# ADC-Front.net
KiCad netlist of a schematic drawn in Altium Designer
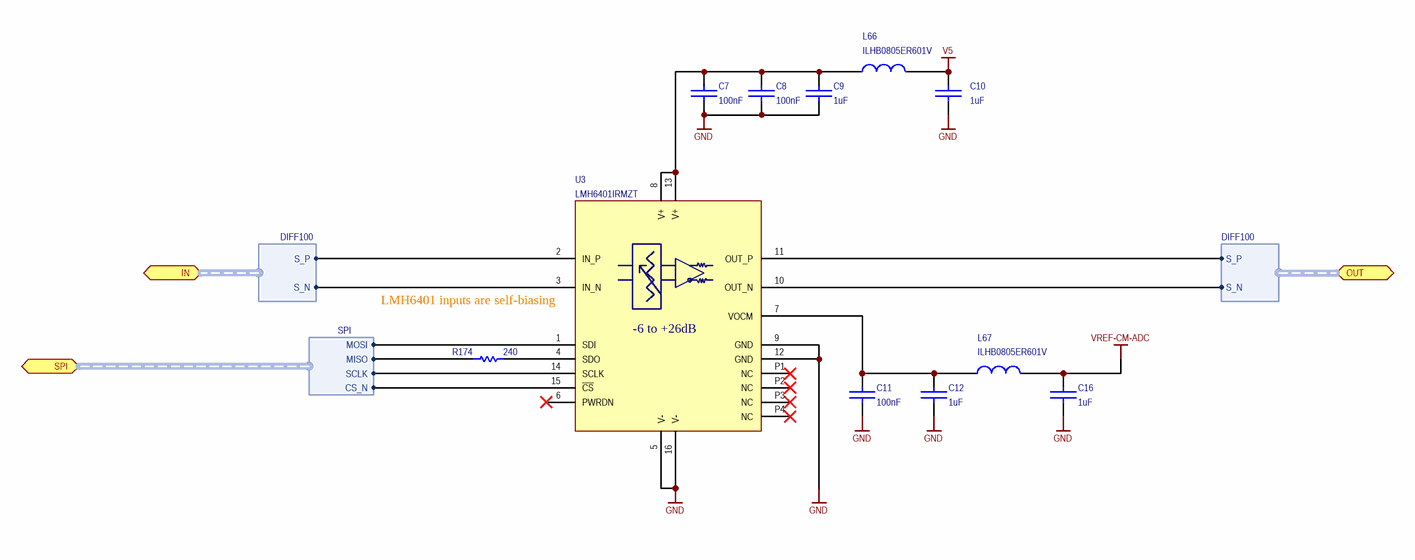
[diagram p0: ADC-Front.SchDoc]

(export (version "E")
  (design (tool "Eeschema 10.0.6"))
  (components
    (comp (ref "C7")
      (value "100nF")
      (footprint "generic:0402")
      (description "Ceramic Capacitor 100nF ±10% 16V X7R 0402")
      (fields (field (name "MANUFACTURER") "Murata") (field (name "VOLTAGE") "16V"))
      (libsource (lib "*") (part "CAP"))
    )
    (comp (ref "C8")
      (value "100nF")
      (footprint "generic:0402")
      (description "Ceramic Capacitor 100nF ±10% 16V X7R 0402")
      (fields (field (name "MANUFACTURER") "Murata") (field (name "VOLTAGE") "16V"))
      (libsource (lib "*") (part "CAP"))
    )
    (comp (ref "C9")
      (value "1uF")
      (footprint "generic:0402")
      (description "Ceramic Capacitor 1uF ±10% 10V X5R 0402")
      (fields (field (name "MANUFACTURER") "Murata") (field (name "TOLERANCE") "±10%"))
      (libsource (lib "*") (part "CAP"))
    )
    (comp (ref "C10")
      (value "1uF")
      (footprint "generic:0402")
      (description "Ceramic Capacitor 1uF ±10% 10V X5R 0402")
      (fields (field (name "MANUFACTURER") "Murata") (field (name "TOLERANCE") "±10%"))
      (libsource (lib "*") (part "CAP"))
    )
    (comp (ref "C11")
      (value "100nF")
      (footprint "generic:0402")
      (description "Ceramic Capacitor 100nF ±10% 16V X7R 0402")
      (fields (field (name "MANUFACTURER") "Murata") (field (name "VOLTAGE") "16V"))
      (libsource (lib "*") (part "CAP"))
    )
    (comp (ref "C12")
      (value "1uF")
      (footprint "generic:0402")
      (description "Ceramic Capacitor 1uF ±10% 10V X5R 0402")
      (fields (field (name "MANUFACTURER") "Murata") (field (name "TOLERANCE") "±10%"))
      (libsource (lib "*") (part "CAP"))
    )
    (comp (ref "C16")
      (value "1uF")
      (footprint "generic:0402")
      (description "Ceramic Capacitor 1uF ±10% 10V X5R 0402")
      (fields (field (name "MANUFACTURER") "Murata") (field (name "TOLERANCE") "±10%"))
      (libsource (lib "*") (part "CAP"))
    )
    (comp (ref "L66")
      (value "ILHB0805ER601V")
      (footprint "0805")
      (description "Ferrite Bead 600-Ohm @ 100MHz 2A 0805")
      (fields (field (name "MANUFACTURER") "Vishay Dale") (field (name "TOLERANCE") "±25%"))
      (libsource (lib "*") (part "INDUCTANCE1"))
    )
    (comp (ref "L67")
      (value "ILHB0805ER601V")
      (footprint "0805")
      (description "Ferrite Bead 600-Ohm @ 100MHz 2A 0805")
      (fields (field (name "MANUFACTURER") "Vishay Dale") (field (name "TOLERANCE") "±25%"))
      (libsource (lib "*") (part "INDUCTANCE1"))
    )
    (comp (ref "R174")
      (value "240")
      (footprint "generic:0402")
      (description "Thick Film Resistor 240 ±1% 0402")
      (fields (field (name "MANUFACTURER") "Panasonic") (field (name "TOLERANCE") "±1%"))
      (libsource (lib "generic") (part "RES 0402"))
    )
    (comp (ref "U3")
      (value "LMH6401IRMZT")
      (footprint "RMZ-UQFN-16")
      (description "Fully Differential Variable Gain Amplifier, DC to 4.5GHz")
      (fields (field (name "MANUFACTURER") "Texas Instruments"))
      (libsource (lib "ti") (part "LMH6401"))
    )
  )
  (nets
    (net (code "3") (name "/CS_N") (class "Default")
      (node (ref "U3") (pin "15") (pinfunction "~{CS}_15") (pintype "passive"))
    )
    (net (code "4") (name "/MISO") (class "Default")
      (node (ref "R174") (pin "1") (pinfunction "1_1") (pintype "passive"))
    )
    (net (code "5") (name "/MOSI") (class "Default")
      (node (ref "U3") (pin "1") (pinfunction "SDI_1") (pintype "passive"))
    )
    (net (code "6") (name "/SCLK") (class "Default")
      (node (ref "U3") (pin "14") (pinfunction "SCLK_14") (pintype "passive"))
    )
    (net (code "9") (name "GND") (class "Default")
      (node (ref "C10") (pin "1") (pinfunction "1_1") (pintype "passive"))
      (node (ref "C11") (pin "1") (pinfunction "1_1") (pintype "passive"))
      (node (ref "C12") (pin "1") (pinfunction "1_1") (pintype "passive"))
      (node (ref "C16") (pin "1") (pinfunction "1_1") (pintype "passive"))
      (node (ref "C7") (pin "1") (pinfunction "1_1") (pintype "passive"))
      (node (ref "C8") (pin "1") (pinfunction "1_1") (pintype "passive"))
      (node (ref "C9") (pin "1") (pinfunction "1_1") (pintype "passive"))
      (node (ref "U3") (pin "12") (pinfunction "GND_12") (pintype "passive"))
      (node (ref "U3") (pin "16") (pinfunction "V-_16") (pintype "passive"))
      (node (ref "U3") (pin "5") (pinfunction "V-_5") (pintype "passive"))
      (node (ref "U3") (pin "9") (pinfunction "GND_9") (pintype "passive"))
    )
    (net (code "10") (name "Net-(C7-Pad2)") (class "Default")
      (node (ref "C7") (pin "2") (pinfunction "2_2") (pintype "passive"))
      (node (ref "C8") (pin "2") (pinfunction "2_2") (pintype "passive"))
      (node (ref "C9") (pin "2") (pinfunction "2_2") (pintype "passive"))
      (node (ref "L66") (pin "1") (pinfunction "1_1") (pintype "passive"))
      (node (ref "U3") (pin "13") (pinfunction "V+_13") (pintype "passive"))
      (node (ref "U3") (pin "8") (pinfunction "V+_8") (pintype "passive"))
    )
    (net (code "11") (name "Net-(U3-SDO)") (class "Default")
      (node (ref "R174") (pin "2") (pinfunction "2_2") (pintype "passive"))
      (node (ref "U3") (pin "4") (pinfunction "SDO_4") (pintype "passive"))
    )
    (net (code "12") (name "Net-(U3-VOCM)") (class "Default")
      (node (ref "C11") (pin "2") (pinfunction "2_2") (pintype "passive"))
      (node (ref "C12") (pin "2") (pinfunction "2_2") (pintype "passive"))
      (node (ref "L67") (pin "1") (pinfunction "1_1") (pintype "passive"))
      (node (ref "U3") (pin "7") (pinfunction "VOCM_7") (pintype "passive"))
    )
    (net (code "13") (name "V5") (class "Default")
      (node (ref "C10") (pin "2") (pinfunction "2_2") (pintype "passive"))
      (node (ref "L66") (pin "2") (pinfunction "2_2") (pintype "passive"))
    )
    (net (code "14") (name "VREF-CM-ADC") (class "Default")
      (node (ref "C16") (pin "2") (pinfunction "2_2") (pintype "passive"))
      (node (ref "L67") (pin "2") (pinfunction "2_2") (pintype "passive"))
    )
    (net (code "15") (name "unconnected-(U3-IN_N-Pad3)") (class "Default")
      (node (ref "U3") (pin "3") (pinfunction "IN_N_3") (pintype "passive"))
    )
    (net (code "16") (name "unconnected-(U3-IN_P-Pad2)") (class "Default")
      (node (ref "U3") (pin "2") (pinfunction "IN_P_2") (pintype "passive"))
    )
    (net (code "17") (name "unconnected-(U3-NC-PadP1)") (class "Default")
      (node (ref "U3") (pin "P1") (pinfunction "NC_P1") (pintype "passive+no_connect"))
    )
    (net (code "18") (name "unconnected-(U3-NC-PadP2)") (class "Default")
      (node (ref "U3") (pin "P2") (pinfunction "NC_P2") (pintype "passive+no_connect"))
    )
    (net (code "19") (name "unconnected-(U3-NC-PadP3)") (class "Default")
      (node (ref "U3") (pin "P3") (pinfunction "NC_P3") (pintype "passive+no_connect"))
    )
    (net (code "20") (name "unconnected-(U3-NC-PadP4)") (class "Default")
      (node (ref "U3") (pin "P4") (pinfunction "NC_P4") (pintype "passive+no_connect"))
    )
    (net (code "21") (name "unconnected-(U3-OUT_N-Pad10)") (class "Default")
      (node (ref "U3") (pin "10") (pinfunction "OUT_N_10") (pintype "passive"))
    )
    (net (code "22") (name "unconnected-(U3-OUT_P-Pad11)") (class "Default")
      (node (ref "U3") (pin "11") (pinfunction "OUT_P_11") (pintype "passive"))
    )
    (net (code "23") (name "unconnected-(U3-PWRDN-Pad6)") (class "Default")
      (node (ref "U3") (pin "6") (pinfunction "PWRDN_6") (pintype "passive+no_connect"))
    )
  )
)
